# Sensor.net
KiCad netlist of a schematic drawn in Altium Designer
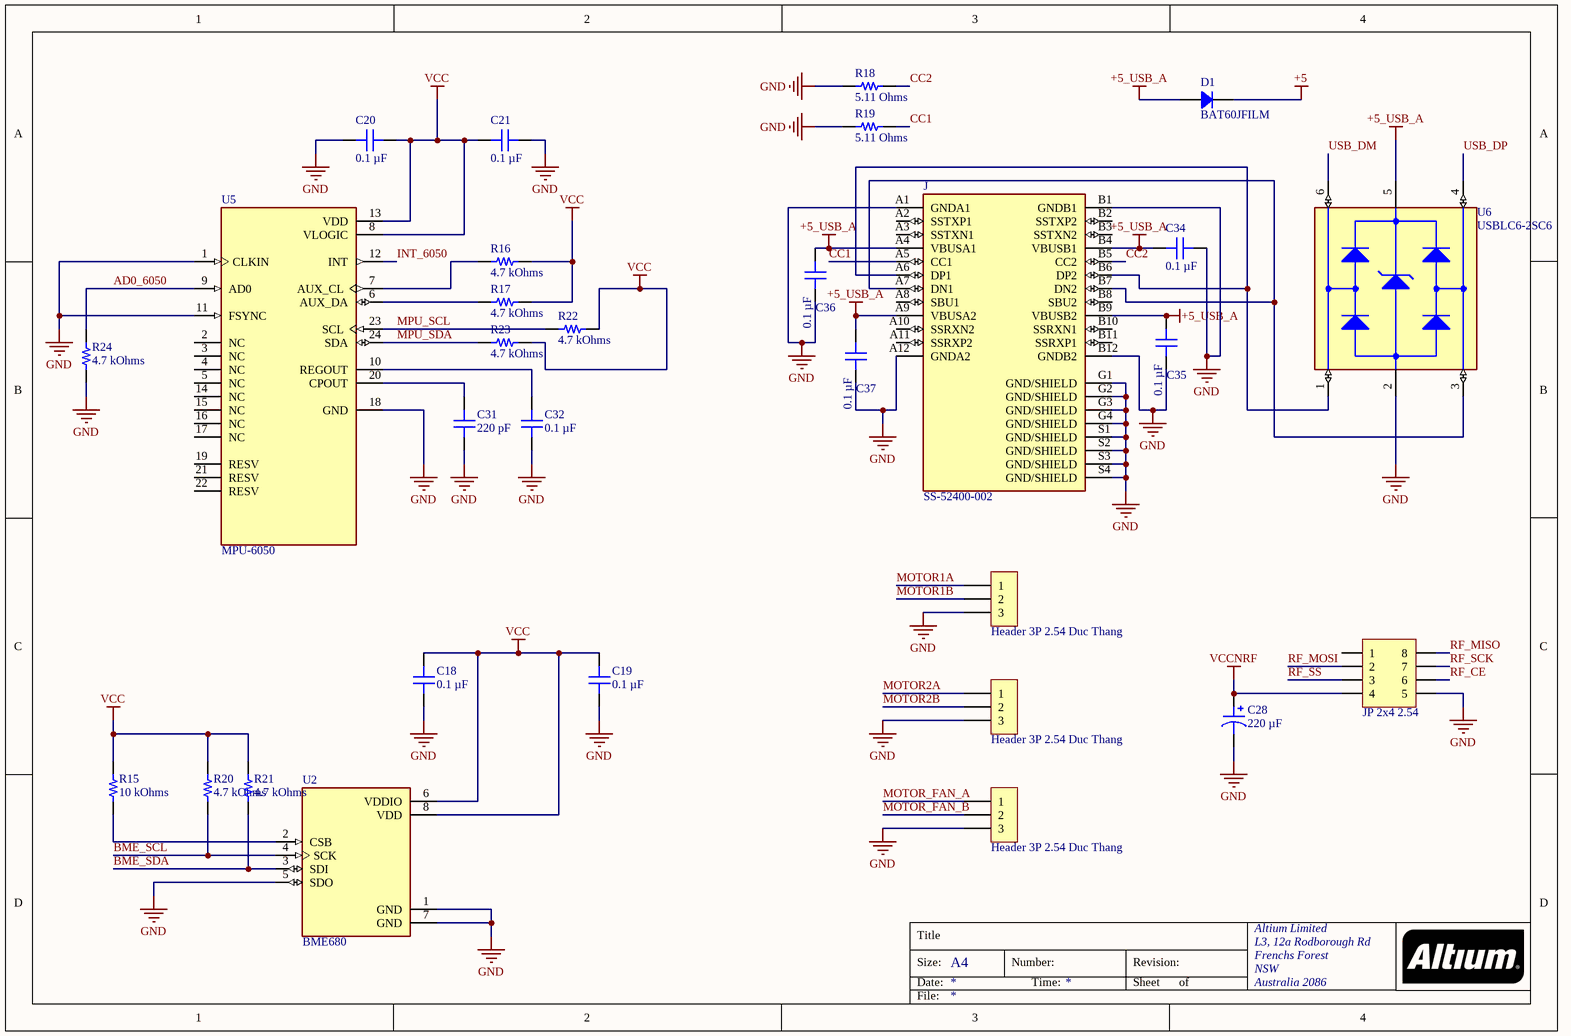
[diagram p0: Sensor.SchDoc]

(export (version "E")
  (design (tool "Eeschema 10.0.6"))
  (components
    (comp (ref "C18")
      (value "0.1 µF")
      (footprint "CAP 0603_1608")
      (description "CAP CER 0.1UF 10V X7R 0603")
      (fields (field (name "PART NUMBER") "C0603C104J8RAC7867") (field (name "MANUFACTURER") "KEMET"))
      (libsource (lib "Celestial Altium Library - altium_library") (part "Capacitor"))
    )
    (comp (ref "C19")
      (value "0.1 µF")
      (footprint "CAP 0603_1608")
      (description "CAP CER 0.1UF 10V X7R 0603")
      (fields (field (name "PART NUMBER") "C0603C104J8RAC7867") (field (name "MANUFACTURER") "KEMET"))
      (libsource (lib "Celestial Altium Library - altium_library") (part "Capacitor"))
    )
    (comp (ref "C20")
      (value "0.1 µF")
      (footprint "CAP 0603_1608")
      (description "CAP CER 0.1UF 10V X7R 0603")
      (fields (field (name "PART NUMBER") "C0603C104J8RAC7867") (field (name "MANUFACTURER") "KEMET"))
      (libsource (lib "Celestial Altium Library - altium_library") (part "Capacitor"))
    )
    (comp (ref "C21")
      (value "0.1 µF")
      (footprint "CAP 0603_1608")
      (description "CAP CER 0.1UF 10V X7R 0603")
      (fields (field (name "PART NUMBER") "C0603C104J8RAC7867") (field (name "MANUFACTURER") "KEMET"))
      (libsource (lib "Celestial Altium Library - altium_library") (part "Capacitor"))
    )
    (comp (ref "C28")
      (value "220 µF")
      (footprint "CAP ALSMD 6.6MM H6.1MM")
      (description "CAP ALUM 220UF 20% 10V SMD")
      (fields (field (name "PART NUMBER") "UCM1A221MCL1GS") (field (name "MANUFACTURER") "Nichicon"))
      (libsource (lib "Celestial Altium Library - altium_library") (part "Polarised Capacitor"))
    )
    (comp (ref "C31")
      (value "220 pF")
      (footprint "CAP 0603_1608")
      (description "CAP CER 220PF 10V X7R 0603")
      (fields (field (name "PART NUMBER") "KGM15AR71A221KT") (field (name "MANUFACTURER") "KYOCERA AVX"))
      (libsource (lib "Celestial Altium Library - altium_library") (part "Capacitor"))
    )
    (comp (ref "C32")
      (value "0.1 µF")
      (footprint "CAP 0603_1608")
      (description "CAP CER 0.1UF 10V X7R 0603")
      (fields (field (name "PART NUMBER") "C0603C104J8RAC7867") (field (name "MANUFACTURER") "KEMET"))
      (libsource (lib "Celestial Altium Library - altium_library") (part "Capacitor"))
    )
    (comp (ref "C34")
      (value "0.1 µF")
      (footprint "CAP 0402_1005")
      (description "CAP CER 0.1UF 10V X7R 0402")
      (fields (field (name "PART NUMBER") "KGM05AR71A104KH") (field (name "MANUFACTURER") "KYOCERA AVX"))
      (libsource (lib "Celestial Altium Library - altium_library") (part "Capacitor"))
    )
    (comp (ref "C35")
      (value "0.1 µF")
      (footprint "CAP 0402_1005")
      (description "CAP CER 0.1UF 10V X7R 0402")
      (fields (field (name "PART NUMBER") "KGM05AR71A104KH") (field (name "MANUFACTURER") "KYOCERA AVX"))
      (libsource (lib "Celestial Altium Library - altium_library") (part "Capacitor"))
    )
    (comp (ref "C36")
      (value "0.1 µF")
      (footprint "CAP 0402_1005")
      (description "CAP CER 0.1UF 10V X7R 0402")
      (fields (field (name "PART NUMBER") "KGM05AR71A104KH") (field (name "MANUFACTURER") "KYOCERA AVX"))
      (libsource (lib "Celestial Altium Library - altium_library") (part "Capacitor"))
    )
    (comp (ref "C37")
      (value "0.1 µF")
      (footprint "CAP 0402_1005")
      (description "CAP CER 0.1UF 10V X7R 0402")
      (fields (field (name "PART NUMBER") "KGM05AR71A104KH") (field (name "MANUFACTURER") "KYOCERA AVX"))
      (libsource (lib "Celestial Altium Library - altium_library") (part "Capacitor"))
    )
    (comp (ref "D1")
      (value "BAT60JFILM")
      (footprint "SOD323")
      (description "DIODE SCHOTTKY 10V 3A SOD323")
      (fields (field (name "MANUFACTURER") "STMicroelectronics"))
      (libsource (lib "Celestial Altium Library - altium_library") (part "Diode"))
    )
    (comp (ref "H3")
      (value "Header 3P 2.54 Duc Thang")
      (footprint "XH2.54M-3")
      (description "Cắm")
      (libsource (lib "Header") (part "Header 3P 2.54 Duc Thang"))
    )
    (comp (ref "H4")
      (value "Header 3P 2.54 Duc Thang")
      (footprint "XH2.54M-3")
      (description "Cắm")
      (libsource (lib "Header") (part "Header 3P 2.54 Duc Thang"))
    )
    (comp (ref "H7")
      (value "Header 3P 2.54 Duc Thang")
      (footprint "XH2.54M-3")
      (description "Cắm")
      (libsource (lib "Header") (part "Header 3P 2.54 Duc Thang"))
    )
    (comp (ref "J")
      (value "SS-52400-002")
      (footprint "BELFUSE_SS-52400-002")
      (description "USB Type-C Connector ¦ 1 Port ¦ Right Angle Receptacle ¦ Shielded ¦ 0.039[1.00mm]")
      (fields (field (name "MF") "Stewart Connector"))
      (libsource (lib "SS-52400-002") (part "SS-52400-002"))
    )
    (comp (ref "JP2")
      (value "JP 2x4 2.54")
      (footprint "JP 2x4 CT")
      (description "Cắm")
      (libsource (lib "Jump") (part "JP 2x4 2.54 Cai Thang"))
    )
    (comp (ref "R15")
      (value "10 kOhms")
      (footprint "RES 0603_1608")
      (description "RES SMD 10K OHM 1% 1/10W 0603")
      (fields (field (name "PART NUMBER") "CRCW060310K0FKEA") (field (name "MANUFACTURER") "Vishay Dale"))
      (libsource (lib "Celestial Altium Library - altium_library") (part "Resistor"))
    )
    (comp (ref "R16")
      (value "4.7 kOhms")
      (footprint "RES 0603_1608")
      (description "RES SMD 4.7K OHM 1% 1/10W 0603")
      (fields (field (name "PART NUMBER") "CR0603-FX-4701ELF") (field (name "MANUFACTURER") "Bourns Inc."))
      (libsource (lib "Celestial Altium Library - altium_library") (part "Resistor"))
    )
    (comp (ref "R17")
      (value "4.7 kOhms")
      (footprint "RES 0603_1608")
      (description "RES SMD 4.7K OHM 1% 1/10W 0603")
      (fields (field (name "PART NUMBER") "CR0603-FX-4701ELF") (field (name "MANUFACTURER") "Bourns Inc."))
      (libsource (lib "Celestial Altium Library - altium_library") (part "Resistor"))
    )
    (comp (ref "R18")
      (value "5.11 Ohms")
      (footprint "RES 0603_1608")
      (description "RES 5.11 OHM 1% 1/10W 0603")
      (fields
        (field (name "PART NUMBER") "RMCF0603FT5R11")
        (field (name "MANUFACTURER") "Stackpole Electronics Inc")
      )
      (libsource (lib "Celestial Altium Library - altium_library") (part "Resistor"))
    )
    (comp (ref "R19")
      (value "5.11 Ohms")
      (footprint "RES 0603_1608")
      (description "RES 5.11 OHM 1% 1/10W 0603")
      (fields
        (field (name "PART NUMBER") "RMCF0603FT5R11")
        (field (name "MANUFACTURER") "Stackpole Electronics Inc")
      )
      (libsource (lib "Celestial Altium Library - altium_library") (part "Resistor"))
    )
    (comp (ref "R20")
      (value "4.7 kOhms")
      (footprint "RES 0603_1608")
      (description "RES 4.7K OHM 1% 1/5W 0603")
      (fields
        (field (name "PART NUMBER") "SG73S1JTTD4701F")
        (field (name "MANUFACTURER") "KOA Speer Electronics, Inc.")
      )
      (libsource (lib "Celestial Altium Library - altium_library") (part "Resistor"))
    )
    (comp (ref "R21")
      (value "4.7 kOhms")
      (footprint "RES 0603_1608")
      (description "RES 4.7K OHM 1% 1/5W 0603")
      (fields
        (field (name "PART NUMBER") "SG73S1JTTD4701F")
        (field (name "MANUFACTURER") "KOA Speer Electronics, Inc.")
      )
      (libsource (lib "Celestial Altium Library - altium_library") (part "Resistor"))
    )
    (comp (ref "R22")
      (value "4.7 kOhms")
      (footprint "RES 0603_1608")
      (description "RES SMD 4.7K OHM 1% 1/10W 0603")
      (fields (field (name "PART NUMBER") "CR0603-FX-4701ELF") (field (name "MANUFACTURER") "Bourns Inc."))
      (libsource (lib "Celestial Altium Library - altium_library") (part "Resistor"))
    )
    (comp (ref "R23")
      (value "4.7 kOhms")
      (footprint "RES 0603_1608")
      (description "RES SMD 4.7K OHM 1% 1/10W 0603")
      (fields (field (name "PART NUMBER") "CR0603-FX-4701ELF") (field (name "MANUFACTURER") "Bourns Inc."))
      (libsource (lib "Celestial Altium Library - altium_library") (part "Resistor"))
    )
    (comp (ref "R24")
      (value "4.7 kOhms")
      (footprint "RES 0603_1608")
      (description "RES SMD 4.7K OHM 1% 1/10W 0603")
      (fields (field (name "PART NUMBER") "CR0603-FX-4701ELF") (field (name "MANUFACTURER") "Bourns Inc."))
      (libsource (lib "Celestial Altium Library - altium_library") (part "Resistor"))
    )
    (comp (ref "U2")
      (value "BME680")
      (footprint "PSON80P300X300X100-8N")
      (description "Gas, Humidity, Pressure, Temperature Sensor IÂ²C, SPI Output")
      (fields (field (name "MF") "Bosch Sensortec"))
      (libsource (lib "BME680") (part "BME680"))
    )
    (comp (ref "U5")
      (value "MPU-6050")
      (footprint "QFN50P400X400X95-24N")
      (description "MPU-6050 series Accelerometer, Gyroscope, 3 Axis Sensor Evaluation Board")
      (fields (field (name "MF") "TDK InvenSense"))
      (libsource (lib "MPU-6050") (part "MPU-6050"))
    )
    (comp (ref "U6")
      (value "USBLC6-2SC6")
      (footprint "SOT95P280X145-6N")
      (description "17V Clamp 5A (8/20Âµs) Ipp Tvs Diode Surface Mount SOT-23-6")
      (fields (field (name "MF") "STMicroelectronics"))
      (libsource (lib "USBLC6-2SC6") (part "USBLC6-2SC6"))
    )
  )
  (nets
    (net (code "1") (name "+5") (class "Default")
      (node (ref "D1") (pin "2") (pinfunction "2_2") (pintype "passive"))
    )
    (net (code "2") (name "+5_USB_A") (class "Default")
      (node (ref "C34") (pin "1") (pinfunction "1_1") (pintype "passive"))
      (node (ref "C35") (pin "1") (pinfunction "1_1") (pintype "passive"))
      (node (ref "C36") (pin "1") (pinfunction "1_1") (pintype "passive"))
      (node (ref "C37") (pin "1") (pinfunction "1_1") (pintype "passive"))
      (node (ref "D1") (pin "1") (pinfunction "1_1") (pintype "passive"))
      (node (ref "J") (pin "A4") (pinfunction "VBUSA1_A4") (pintype "power_in"))
      (node (ref "J") (pin "A9") (pinfunction "VBUSA2_A9") (pintype "power_in"))
      (node (ref "J") (pin "B4") (pinfunction "VBUSB1_B4") (pintype "power_in"))
      (node (ref "J") (pin "B9") (pinfunction "VBUSB2_B9") (pintype "power_in"))
      (node (ref "U6") (pin "5") (pinfunction "VBUS_5") (pintype "power_in"))
    )
    (net (code "3") (name "/AD0_6050") (class "Default")
      (node (ref "R24") (pin "2") (pinfunction "2_2") (pintype "passive"))
      (node (ref "U5") (pin "9") (pinfunction "AD0_9") (pintype "input"))
    )
    (net (code "4") (name "/BME_SCL") (class "Default")
      (node (ref "R20") (pin "1") (pinfunction "1_1") (pintype "passive"))
      (node (ref "U2") (pin "4") (pinfunction "SCK_4") (pintype "input"))
    )
    (net (code "5") (name "/BME_SDA") (class "Default")
      (node (ref "R21") (pin "1") (pinfunction "1_1") (pintype "passive"))
      (node (ref "U2") (pin "3") (pinfunction "SDI_3") (pintype "bidirectional"))
    )
    (net (code "6") (name "/CC1") (class "Default")
      (node (ref "J") (pin "A5") (pinfunction "CC1_A5") (pintype "bidirectional"))
      (node (ref "R19") (pin "2") (pinfunction "2_2") (pintype "passive"))
    )
    (net (code "7") (name "/CC2") (class "Default")
      (node (ref "J") (pin "B5") (pinfunction "CC2_B5") (pintype "bidirectional"))
      (node (ref "R18") (pin "2") (pinfunction "2_2") (pintype "passive"))
    )
    (net (code "8") (name "/INT_6050") (class "Default")
      (node (ref "U5") (pin "12") (pinfunction "INT_12") (pintype "output"))
    )
    (net (code "9") (name "/MOTOR1A") (class "Default")
      (node (ref "H7") (pin "1") (pinfunction "1_1") (pintype "passive"))
    )
    (net (code "10") (name "/MOTOR1B") (class "Default")
      (node (ref "H7") (pin "2") (pinfunction "2_2") (pintype "passive"))
    )
    (net (code "11") (name "/MOTOR2A") (class "Default")
      (node (ref "H3") (pin "1") (pinfunction "1_1") (pintype "passive"))
    )
    (net (code "12") (name "/MOTOR2B") (class "Default")
      (node (ref "H3") (pin "2") (pinfunction "2_2") (pintype "passive"))
    )
    (net (code "13") (name "/MOTOR_FAN_A") (class "Default")
      (node (ref "H4") (pin "1") (pinfunction "1_1") (pintype "passive"))
    )
    (net (code "14") (name "/MOTOR_FAN_B") (class "Default")
      (node (ref "H4") (pin "2") (pinfunction "2_2") (pintype "passive"))
    )
    (net (code "15") (name "/MPU_SCL") (class "Default")
      (node (ref "R22") (pin "1") (pinfunction "1_1") (pintype "passive"))
      (node (ref "U5") (pin "23") (pinfunction "SCL_23") (pintype "input"))
    )
    (net (code "16") (name "/MPU_SDA") (class "Default")
      (node (ref "R23") (pin "1") (pinfunction "1_1") (pintype "passive"))
      (node (ref "U5") (pin "24") (pinfunction "SDA_24") (pintype "bidirectional"))
    )
    (net (code "17") (name "/RF_CE") (class "Default")
      (node (ref "JP2") (pin "6") (pinfunction "6_6") (pintype "passive"))
    )
    (net (code "18") (name "/RF_MISO") (class "Default")
      (node (ref "JP2") (pin "8") (pinfunction "8_8") (pintype "passive"))
    )
    (net (code "19") (name "/RF_MOSI") (class "Default")
      (node (ref "JP2") (pin "2") (pinfunction "2_2") (pintype "passive"))
    )
    (net (code "20") (name "/RF_SCK") (class "Default")
      (node (ref "JP2") (pin "7") (pinfunction "7_7") (pintype "passive"))
    )
    (net (code "21") (name "/RF_SS") (class "Default")
      (node (ref "JP2") (pin "3") (pinfunction "3_3") (pintype "passive"))
    )
    (net (code "22") (name "/USB_DM") (class "Default")
      (node (ref "U6") (pin "6") (pinfunction "I/O1_OUT_6") (pintype "bidirectional"))
    )
    (net (code "23") (name "/USB_DP") (class "Default")
      (node (ref "U6") (pin "4") (pinfunction "I/O2_OUT_4") (pintype "bidirectional"))
    )
    (net (code "24") (name "GND") (class "Default")
      (node (ref "C18") (pin "1") (pinfunction "1_1") (pintype "passive"))
      (node (ref "C19") (pin "1") (pinfunction "1_1") (pintype "passive"))
      (node (ref "C20") (pin "1") (pinfunction "1_1") (pintype "passive"))
      (node (ref "C21") (pin "2") (pinfunction "2_2") (pintype "passive"))
      (node (ref "C28") (pin "2") (pinfunction "2_2") (pintype "passive"))
      (node (ref "C31") (pin "1") (pinfunction "1_1") (pintype "passive"))
      (node (ref "C32") (pin "1") (pinfunction "1_1") (pintype "passive"))
      (node (ref "C34") (pin "2") (pinfunction "2_2") (pintype "passive"))
      (node (ref "C35") (pin "2") (pinfunction "2_2") (pintype "passive"))
      (node (ref "C36") (pin "2") (pinfunction "2_2") (pintype "passive"))
      (node (ref "C37") (pin "2") (pinfunction "2_2") (pintype "passive"))
      (node (ref "H3") (pin "3") (pinfunction "3_3") (pintype "passive"))
      (node (ref "H4") (pin "3") (pinfunction "3_3") (pintype "passive"))
      (node (ref "H7") (pin "3") (pinfunction "3_3") (pintype "passive"))
      (node (ref "J") (pin "A1") (pinfunction "GNDA1_A1") (pintype "power_in"))
      (node (ref "J") (pin "A12") (pinfunction "GNDA2_A12") (pintype "power_in"))
      (node (ref "J") (pin "B1") (pinfunction "GNDB1_B1") (pintype "power_in"))
      (node (ref "J") (pin "B12") (pinfunction "GNDB2_B12") (pintype "power_in"))
      (node (ref "J") (pin "G1") (pinfunction "GND/SHIELD_G1") (pintype "power_in"))
      (node (ref "J") (pin "G2") (pinfunction "GND/SHIELD_G2") (pintype "power_in"))
      (node (ref "J") (pin "G3") (pinfunction "GND/SHIELD_G3") (pintype "power_in"))
      (node (ref "J") (pin "G4") (pinfunction "GND/SHIELD_G4") (pintype "power_in"))
      (node (ref "J") (pin "S1") (pinfunction "GND/SHIELD_S1") (pintype "power_in"))
      (node (ref "J") (pin "S2") (pinfunction "GND/SHIELD_S2") (pintype "power_in"))
      (node (ref "J") (pin "S3") (pinfunction "GND/SHIELD_S3") (pintype "power_in"))
      (node (ref "J") (pin "S4") (pinfunction "GND/SHIELD_S4") (pintype "power_in"))
      (node (ref "JP2") (pin "5") (pinfunction "5_5") (pintype "passive"))
      (node (ref "R18") (pin "1") (pinfunction "1_1") (pintype "passive"))
      (node (ref "R19") (pin "1") (pinfunction "1_1") (pintype "passive"))
      (node (ref "R24") (pin "1") (pinfunction "1_1") (pintype "passive"))
      (node (ref "U2") (pin "1") (pinfunction "GND_1") (pintype "power_in"))
      (node (ref "U2") (pin "5") (pinfunction "SDO_5") (pintype "bidirectional"))
      (node (ref "U2") (pin "7") (pinfunction "GND_7") (pintype "power_in"))
      (node (ref "U5") (pin "1") (pinfunction "CLKIN_1") (pintype "input"))
      (node (ref "U5") (pin "11") (pinfunction "FSYNC_11") (pintype "input"))
      (node (ref "U5") (pin "18") (pinfunction "GND_18") (pintype "power_in"))
      (node (ref "U6") (pin "2") (pinfunction "GND_2") (pintype "power_in"))
    )
    (net (code "25") (name "Net-(J-DN1)") (class "Default")
      (node (ref "J") (pin "A7") (pinfunction "DN1_A7") (pintype "bidirectional"))
      (node (ref "J") (pin "B7") (pinfunction "DN2_B7") (pintype "bidirectional"))
      (node (ref "U6") (pin "3") (pinfunction "I/O2_IN_3") (pintype "bidirectional"))
    )
    (net (code "26") (name "Net-(J-DP1)") (class "Default")
      (node (ref "J") (pin "A6") (pinfunction "DP1_A6") (pintype "bidirectional"))
      (node (ref "J") (pin "B6") (pinfunction "DP2_B6") (pintype "bidirectional"))
      (node (ref "U6") (pin "1") (pinfunction "I/O1_IN_1") (pintype "bidirectional"))
    )
    (net (code "27") (name "Net-(U2-CSB)") (class "Default")
      (node (ref "R15") (pin "1") (pinfunction "1_1") (pintype "passive"))
      (node (ref "U2") (pin "2") (pinfunction "CSB_2") (pintype "input"))
    )
    (net (code "28") (name "Net-(U5-AUX_CL)") (class "Default")
      (node (ref "R16") (pin "1") (pinfunction "1_1") (pintype "passive"))
      (node (ref "U5") (pin "7") (pinfunction "AUX_CL_7") (pintype "output"))
    )
    (net (code "29") (name "Net-(U5-AUX_DA)") (class "Default")
      (node (ref "R17") (pin "1") (pinfunction "1_1") (pintype "passive"))
      (node (ref "U5") (pin "6") (pinfunction "AUX_DA_6") (pintype "bidirectional"))
    )
    (net (code "30") (name "Net-(U5-CPOUT)") (class "Default")
      (node (ref "C31") (pin "2") (pinfunction "2_2") (pintype "passive"))
      (node (ref "U5") (pin "20") (pinfunction "CPOUT_20") (pintype "passive"))
    )
    (net (code "31") (name "Net-(U5-REGOUT)") (class "Default")
      (node (ref "C32") (pin "2") (pinfunction "2_2") (pintype "passive"))
      (node (ref "U5") (pin "10") (pinfunction "REGOUT_10") (pintype "passive"))
    )
    (net (code "32") (name "VCC") (class "Default")
      (node (ref "C18") (pin "2") (pinfunction "2_2") (pintype "passive"))
      (node (ref "C19") (pin "2") (pinfunction "2_2") (pintype "passive"))
      (node (ref "C20") (pin "2") (pinfunction "2_2") (pintype "passive"))
      (node (ref "C21") (pin "1") (pinfunction "1_1") (pintype "passive"))
      (node (ref "R15") (pin "2") (pinfunction "2_2") (pintype "passive"))
      (node (ref "R16") (pin "2") (pinfunction "2_2") (pintype "passive"))
      (node (ref "R17") (pin "2") (pinfunction "2_2") (pintype "passive"))
      (node (ref "R20") (pin "2") (pinfunction "2_2") (pintype "passive"))
      (node (ref "R21") (pin "2") (pinfunction "2_2") (pintype "passive"))
      (node (ref "R22") (pin "2") (pinfunction "2_2") (pintype "passive"))
      (node (ref "R23") (pin "2") (pinfunction "2_2") (pintype "passive"))
      (node (ref "U2") (pin "6") (pinfunction "VDDIO_6") (pintype "power_in"))
      (node (ref "U2") (pin "8") (pinfunction "VDD_8") (pintype "power_in"))
      (node (ref "U5") (pin "13") (pinfunction "VDD_13") (pintype "power_in"))
      (node (ref "U5") (pin "8") (pinfunction "VLOGIC_8") (pintype "power_in"))
    )
    (net (code "33") (name "VCCNRF") (class "Default")
      (node (ref "C28") (pin "1") (pinfunction "1_1") (pintype "passive"))
      (node (ref "JP2") (pin "4") (pinfunction "4_4") (pintype "passive"))
    )
    (net (code "34") (name "unconnected-(J-SBU1-PadA8)") (class "Default")
      (node (ref "J") (pin "A8") (pinfunction "SBU1_A8") (pintype "bidirectional"))
    )
    (net (code "35") (name "unconnected-(J-SBU2-PadB8)") (class "Default")
      (node (ref "J") (pin "B8") (pinfunction "SBU2_B8") (pintype "bidirectional"))
    )
    (net (code "36") (name "unconnected-(J-SSRXN1-PadB10)") (class "Default")
      (node (ref "J") (pin "B10") (pinfunction "SSRXN1_B10") (pintype "bidirectional"))
    )
    (net (code "37") (name "unconnected-(J-SSRXN2-PadA10)") (class "Default")
      (node (ref "J") (pin "A10") (pinfunction "SSRXN2_A10") (pintype "bidirectional"))
    )
    (net (code "38") (name "unconnected-(J-SSRXP1-PadB11)") (class "Default")
      (node (ref "J") (pin "B11") (pinfunction "SSRXP1_B11") (pintype "bidirectional"))
    )
    (net (code "39") (name "unconnected-(J-SSRXP2-PadA11)") (class "Default")
      (node (ref "J") (pin "A11") (pinfunction "SSRXP2_A11") (pintype "bidirectional"))
    )
    (net (code "40") (name "unconnected-(J-SSTXN1-PadA3)") (class "Default")
      (node (ref "J") (pin "A3") (pinfunction "SSTXN1_A3") (pintype "bidirectional"))
    )
    (net (code "41") (name "unconnected-(J-SSTXN2-PadB3)") (class "Default")
      (node (ref "J") (pin "B3") (pinfunction "SSTXN2_B3") (pintype "bidirectional"))
    )
    (net (code "42") (name "unconnected-(J-SSTXP1-PadA2)") (class "Default")
      (node (ref "J") (pin "A2") (pinfunction "SSTXP1_A2") (pintype "bidirectional"))
    )
    (net (code "43") (name "unconnected-(J-SSTXP2-PadB2)") (class "Default")
      (node (ref "J") (pin "B2") (pinfunction "SSTXP2_B2") (pintype "bidirectional"))
    )
    (net (code "44") (name "unconnected-(JP2-Pad1)") (class "Default")
      (node (ref "JP2") (pin "1") (pinfunction "1_1") (pintype "passive"))
    )
    (net (code "45") (name "unconnected-(U5-NC-Pad2)") (class "Default")
      (node (ref "U5") (pin "2") (pinfunction "NC_2") (pintype "passive"))
    )
    (net (code "46") (name "unconnected-(U5-NC-Pad3)") (class "Default")
      (node (ref "U5") (pin "3") (pinfunction "NC_3") (pintype "passive"))
    )
    (net (code "47") (name "unconnected-(U5-NC-Pad4)") (class "Default")
      (node (ref "U5") (pin "4") (pinfunction "NC_4") (pintype "passive"))
    )
    (net (code "48") (name "unconnected-(U5-NC-Pad5)") (class "Default")
      (node (ref "U5") (pin "5") (pinfunction "NC_5") (pintype "passive"))
    )
    (net (code "49") (name "unconnected-(U5-NC-Pad14)") (class "Default")
      (node (ref "U5") (pin "14") (pinfunction "NC_14") (pintype "passive"))
    )
    (net (code "50") (name "unconnected-(U5-NC-Pad15)") (class "Default")
      (node (ref "U5") (pin "15") (pinfunction "NC_15") (pintype "passive"))
    )
    (net (code "51") (name "unconnected-(U5-NC-Pad16)") (class "Default")
      (node (ref "U5") (pin "16") (pinfunction "NC_16") (pintype "passive"))
    )
    (net (code "52") (name "unconnected-(U5-NC-Pad17)") (class "Default")
      (node (ref "U5") (pin "17") (pinfunction "NC_17") (pintype "passive"))
    )
    (net (code "53") (name "unconnected-(U5-RESV-Pad19)") (class "Default")
      (node (ref "U5") (pin "19") (pinfunction "RESV_19") (pintype "passive"))
    )
    (net (code "54") (name "unconnected-(U5-RESV-Pad21)") (class "Default")
      (node (ref "U5") (pin "21") (pinfunction "RESV_21") (pintype "passive"))
    )
    (net (code "55") (name "unconnected-(U5-RESV-Pad22)") (class "Default")
      (node (ref "U5") (pin "22") (pinfunction "RESV_22") (pintype "passive"))
    )
  )
)
